# bqcopter.net
KiCad netlist of a schematic drawn in EAGLE
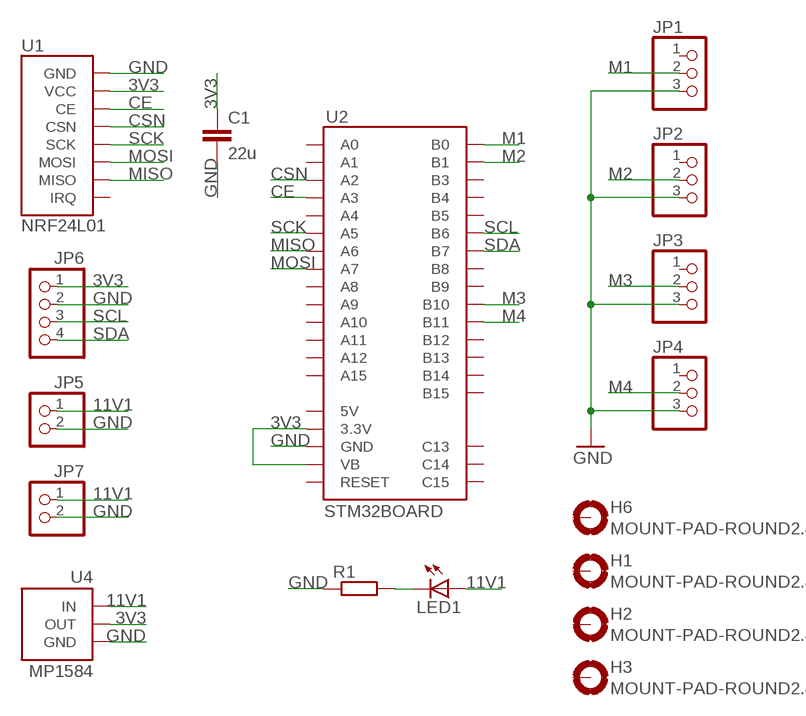
[diagram p0: schematic, sheet 1]

(export (version "E")
  (design (tool "Eeschema 10.0.6"))
  (components
    (comp (ref "C1")
      (value "22u")
      (footprint "eagle-import:C0805")
      (libsource (lib "eagle-import") (part "C-EUC0805"))
    )
    (comp (ref "H1")
      (value "MOUNT-PAD-ROUND2.8")
      (footprint "eagle-import:2,8-PAD")
      (libsource (lib "eagle-import") (part "MOUNT-PAD-ROUND2.8"))
    )
    (comp (ref "H2")
      (value "MOUNT-PAD-ROUND2.8")
      (footprint "eagle-import:2,8-PAD")
      (libsource (lib "eagle-import") (part "MOUNT-PAD-ROUND2.8"))
    )
    (comp (ref "H3")
      (value "MOUNT-PAD-ROUND2.8")
      (footprint "eagle-import:2,8-PAD")
      (libsource (lib "eagle-import") (part "MOUNT-PAD-ROUND2.8"))
    )
    (comp (ref "H6")
      (value "MOUNT-PAD-ROUND2.8")
      (footprint "eagle-import:2,8-PAD")
      (libsource (lib "eagle-import") (part "MOUNT-PAD-ROUND2.8"))
    )
    (comp (ref "JP1")
      (value "PINHD-1X3")
      (footprint "eagle-import:1X03")
      (libsource (lib "eagle-import") (part "PINHD-1X3"))
    )
    (comp (ref "JP2")
      (value "PINHD-1X3")
      (footprint "eagle-import:1X03")
      (libsource (lib "eagle-import") (part "PINHD-1X3"))
    )
    (comp (ref "JP3")
      (value "PINHD-1X3")
      (footprint "eagle-import:1X03")
      (libsource (lib "eagle-import") (part "PINHD-1X3"))
    )
    (comp (ref "JP4")
      (value "PINHD-1X3")
      (footprint "eagle-import:1X03")
      (libsource (lib "eagle-import") (part "PINHD-1X3"))
    )
    (comp (ref "JP5")
      (value "PINHD-1X2")
      (footprint "eagle-import:1X02")
      (libsource (lib "eagle-import") (part "PINHD-1X2"))
    )
    (comp (ref "JP6")
      (value "PINHD-1X4")
      (footprint "eagle-import:1X04")
      (libsource (lib "eagle-import") (part "PINHD-1X4"))
    )
    (comp (ref "JP7")
      (value "PINHD-1X2")
      (footprint "eagle-import:1X02")
      (libsource (lib "eagle-import") (part "PINHD-1X2"))
    )
    (comp (ref "LED1")
      (value "LED3MM")
      (footprint "eagle-import:LED3MM")
      (libsource (lib "eagle-import") (part "LED3MM"))
    )
    (comp (ref "R1")
      (value "R-EU_M0805")
      (footprint "eagle-import:M0805")
      (libsource (lib "eagle-import") (part "R-EU_M0805"))
    )
    (comp (ref "U1")
      (value "NRF24L01")
      (footprint "eagle-import:NRF24L01")
      (libsource (lib "eagle-import") (part "NRF24L01"))
    )
    (comp (ref "U2")
      (value "STM32BOARD")
      (footprint "eagle-import:STM32BOARD")
      (libsource (lib "eagle-import") (part "STM32BOARD"))
    )
    (comp (ref "U4")
      (value "MP1584")
      (footprint "eagle-import:MP1584")
      (libsource (lib "eagle-import") (part "MP1584"))
    )
  )
  (nets
    (net (code "1") (name "/3V3") (class "Default")
      (node (ref "C1") (pin "1") (pinfunction "1_1") (pintype "passive"))
      (node (ref "JP6") (pin "1") (pinfunction "1_1") (pintype "passive"))
      (node (ref "U1") (pin "2") (pinfunction "VCC_2") (pintype "bidirectional"))
      (node (ref "U2") (pin "3.3V_1") (pinfunction "3.3V_3.3V_1") (pintype "bidirectional"))
      (node (ref "U2") (pin "3.3V_2") (pinfunction "3.3V_3.3V_2") (pintype "bidirectional"))
      (node (ref "U2") (pin "VB") (pinfunction "VB_VB") (pintype "bidirectional"))
      (node (ref "U4") (pin "OUT+1") (pinfunction "OUT_OUT+1") (pintype "bidirectional"))
      (node (ref "U4") (pin "OUT+2") (pinfunction "OUT_OUT+2") (pintype "bidirectional"))
    )
    (net (code "2") (name "/11V1") (class "Default")
      (node (ref "JP5") (pin "1") (pinfunction "1_1") (pintype "passive"))
      (node (ref "JP7") (pin "1") (pinfunction "1_1") (pintype "passive"))
      (node (ref "LED1") (pin "A") (pinfunction "A_A") (pintype "passive"))
      (node (ref "U4") (pin "IN+1") (pinfunction "IN_IN+1") (pintype "bidirectional"))
      (node (ref "U4") (pin "IN+2") (pinfunction "IN_IN+2") (pintype "bidirectional"))
    )
    (net (code "3") (name "/CE") (class "Default")
      (node (ref "U1") (pin "3") (pinfunction "CE_3") (pintype "bidirectional"))
      (node (ref "U2") (pin "A3") (pinfunction "A3_A3") (pintype "bidirectional"))
    )
    (net (code "4") (name "/CSN") (class "Default")
      (node (ref "U1") (pin "4") (pinfunction "CSN_4") (pintype "bidirectional"))
      (node (ref "U2") (pin "A2") (pinfunction "A2_A2") (pintype "bidirectional"))
    )
    (net (code "5") (name "/M1") (class "Default")
      (node (ref "JP1") (pin "2") (pinfunction "2_2") (pintype "passive"))
      (node (ref "U2") (pin "B0") (pinfunction "B0_B0") (pintype "bidirectional"))
    )
    (net (code "6") (name "/M2") (class "Default")
      (node (ref "JP2") (pin "2") (pinfunction "2_2") (pintype "passive"))
      (node (ref "U2") (pin "B1") (pinfunction "B1_B1") (pintype "bidirectional"))
    )
    (net (code "7") (name "/M3") (class "Default")
      (node (ref "JP3") (pin "2") (pinfunction "2_2") (pintype "passive"))
      (node (ref "U2") (pin "B10") (pinfunction "B10_B10") (pintype "bidirectional"))
    )
    (net (code "8") (name "/M4") (class "Default")
      (node (ref "JP4") (pin "2") (pinfunction "2_2") (pintype "passive"))
      (node (ref "U2") (pin "B11") (pinfunction "B11_B11") (pintype "bidirectional"))
    )
    (net (code "9") (name "/MISO") (class "Default")
      (node (ref "U1") (pin "7") (pinfunction "MISO_7") (pintype "bidirectional"))
      (node (ref "U2") (pin "A6") (pinfunction "A6_A6") (pintype "bidirectional"))
    )
    (net (code "10") (name "/MOSI") (class "Default")
      (node (ref "U1") (pin "6") (pinfunction "MOSI_6") (pintype "bidirectional"))
      (node (ref "U2") (pin "A7") (pinfunction "A7_A7") (pintype "bidirectional"))
    )
    (net (code "11") (name "/SCK") (class "Default")
      (node (ref "U1") (pin "5") (pinfunction "SCK_5") (pintype "bidirectional"))
      (node (ref "U2") (pin "A5") (pinfunction "A5_A5") (pintype "bidirectional"))
    )
    (net (code "12") (name "/SCL") (class "Default")
      (node (ref "JP6") (pin "3") (pinfunction "3_3") (pintype "passive"))
      (node (ref "U2") (pin "B6") (pinfunction "B6_B6") (pintype "bidirectional"))
    )
    (net (code "13") (name "/SDA") (class "Default")
      (node (ref "JP6") (pin "4") (pinfunction "4_4") (pintype "passive"))
      (node (ref "U2") (pin "B7") (pinfunction "B7_B7") (pintype "bidirectional"))
    )
    (net (code "14") (name "GND") (class "Default")
      (node (ref "C1") (pin "2") (pinfunction "2_2") (pintype "passive"))
      (node (ref "JP1") (pin "3") (pinfunction "3_3") (pintype "passive"))
      (node (ref "JP2") (pin "3") (pinfunction "3_3") (pintype "passive"))
      (node (ref "JP3") (pin "3") (pinfunction "3_3") (pintype "passive"))
      (node (ref "JP4") (pin "3") (pinfunction "3_3") (pintype "passive"))
      (node (ref "JP5") (pin "2") (pinfunction "2_2") (pintype "passive"))
      (node (ref "JP6") (pin "2") (pinfunction "2_2") (pintype "passive"))
      (node (ref "JP7") (pin "2") (pinfunction "2_2") (pintype "passive"))
      (node (ref "R1") (pin "1") (pinfunction "1_1") (pintype "passive"))
      (node (ref "U1") (pin "1") (pinfunction "GND_1") (pintype "bidirectional"))
      (node (ref "U2") (pin "GND_1") (pinfunction "GND_GND_1") (pintype "bidirectional"))
      (node (ref "U2") (pin "GND_2") (pinfunction "GND_GND_2") (pintype "bidirectional"))
      (node (ref "U2") (pin "GND_3") (pinfunction "GND_GND_3") (pintype "bidirectional"))
      (node (ref "U4") (pin "IN-1") (pinfunction "GND_IN-1") (pintype "bidirectional"))
      (node (ref "U4") (pin "IN-2") (pinfunction "GND_IN-2") (pintype "bidirectional"))
      (node (ref "U4") (pin "OUT-1") (pinfunction "GND_OUT-1") (pintype "bidirectional"))
      (node (ref "U4") (pin "OUT-2") (pinfunction "GND_OUT-2") (pintype "bidirectional"))
    )
    (net (code "15") (name "Net-(LED1-C)") (class "Default")
      (node (ref "LED1") (pin "K") (pinfunction "C_K") (pintype "passive"))
      (node (ref "R1") (pin "2") (pinfunction "2_2") (pintype "passive"))
    )
    (net (code "16") (name "unconnected-(H1-MOUNT-PadB2,8)") (class "Default")
      (node (ref "H1") (pin "B2,8") (pinfunction "MOUNT_B2,8") (pintype "passive"))
    )
    (net (code "17") (name "unconnected-(H2-MOUNT-PadB2,8)") (class "Default")
      (node (ref "H2") (pin "B2,8") (pinfunction "MOUNT_B2,8") (pintype "passive"))
    )
    (net (code "18") (name "unconnected-(H3-MOUNT-PadB2,8)") (class "Default")
      (node (ref "H3") (pin "B2,8") (pinfunction "MOUNT_B2,8") (pintype "passive"))
    )
    (net (code "19") (name "unconnected-(H6-MOUNT-PadB2,8)") (class "Default")
      (node (ref "H6") (pin "B2,8") (pinfunction "MOUNT_B2,8") (pintype "passive"))
    )
    (net (code "20") (name "unconnected-(JP1-Pad1)") (class "Default")
      (node (ref "JP1") (pin "1") (pinfunction "1_1") (pintype "passive"))
    )
    (net (code "21") (name "unconnected-(JP2-Pad1)") (class "Default")
      (node (ref "JP2") (pin "1") (pinfunction "1_1") (pintype "passive"))
    )
    (net (code "22") (name "unconnected-(JP3-Pad1)") (class "Default")
      (node (ref "JP3") (pin "1") (pinfunction "1_1") (pintype "passive"))
    )
    (net (code "23") (name "unconnected-(JP4-Pad1)") (class "Default")
      (node (ref "JP4") (pin "1") (pinfunction "1_1") (pintype "passive"))
    )
    (net (code "24") (name "unconnected-(U1-IRQ-Pad8)") (class "Default")
      (node (ref "U1") (pin "8") (pinfunction "IRQ_8") (pintype "bidirectional"))
    )
    (net (code "25") (name "unconnected-(U2-Pad5V)") (class "Default")
      (node (ref "U2") (pin "5V") (pinfunction "5V_5V") (pintype "bidirectional"))
    )
    (net (code "26") (name "unconnected-(U2-PadA0)") (class "Default")
      (node (ref "U2") (pin "A0") (pinfunction "A0_A0") (pintype "bidirectional"))
    )
    (net (code "27") (name "unconnected-(U2-PadA1)") (class "Default")
      (node (ref "U2") (pin "A1") (pinfunction "A1_A1") (pintype "bidirectional"))
    )
    (net (code "28") (name "unconnected-(U2-PadA4)") (class "Default")
      (node (ref "U2") (pin "A4") (pinfunction "A4_A4") (pintype "bidirectional"))
    )
    (net (code "29") (name "unconnected-(U2-PadA8)") (class "Default")
      (node (ref "U2") (pin "A8") (pinfunction "A8_A8") (pintype "bidirectional"))
    )
    (net (code "30") (name "unconnected-(U2-PadA9)") (class "Default")
      (node (ref "U2") (pin "A9") (pinfunction "A9_A9") (pintype "bidirectional"))
    )
    (net (code "31") (name "unconnected-(U2-PadA10)") (class "Default")
      (node (ref "U2") (pin "A10") (pinfunction "A10_A10") (pintype "bidirectional"))
    )
    (net (code "32") (name "unconnected-(U2-PadA11)") (class "Default")
      (node (ref "U2") (pin "A11") (pinfunction "A11_A11") (pintype "bidirectional"))
    )
    (net (code "33") (name "unconnected-(U2-PadA12)") (class "Default")
      (node (ref "U2") (pin "A12") (pinfunction "A12_A12") (pintype "bidirectional"))
    )
    (net (code "34") (name "unconnected-(U2-PadA15)") (class "Default")
      (node (ref "U2") (pin "A15") (pinfunction "A15_A15") (pintype "bidirectional"))
    )
    (net (code "35") (name "unconnected-(U2-PadB3)") (class "Default")
      (node (ref "U2") (pin "B3") (pinfunction "B3_B3") (pintype "bidirectional"))
    )
    (net (code "36") (name "unconnected-(U2-PadB4)") (class "Default")
      (node (ref "U2") (pin "B4") (pinfunction "B4_B4") (pintype "bidirectional"))
    )
    (net (code "37") (name "unconnected-(U2-PadB5)") (class "Default")
      (node (ref "U2") (pin "B5") (pinfunction "B5_B5") (pintype "bidirectional"))
    )
    (net (code "38") (name "unconnected-(U2-PadB8)") (class "Default")
      (node (ref "U2") (pin "B8") (pinfunction "B8_B8") (pintype "bidirectional"))
    )
    (net (code "39") (name "unconnected-(U2-PadB9)") (class "Default")
      (node (ref "U2") (pin "B9") (pinfunction "B9_B9") (pintype "bidirectional"))
    )
    (net (code "40") (name "unconnected-(U2-PadB12)") (class "Default")
      (node (ref "U2") (pin "B12") (pinfunction "B12_B12") (pintype "bidirectional"))
    )
    (net (code "41") (name "unconnected-(U2-PadB13)") (class "Default")
      (node (ref "U2") (pin "B13") (pinfunction "B13_B13") (pintype "bidirectional"))
    )
    (net (code "42") (name "unconnected-(U2-PadB14)") (class "Default")
      (node (ref "U2") (pin "B14") (pinfunction "B14_B14") (pintype "bidirectional"))
    )
    (net (code "43") (name "unconnected-(U2-PadB15)") (class "Default")
      (node (ref "U2") (pin "B15") (pinfunction "B15_B15") (pintype "bidirectional"))
    )
    (net (code "44") (name "unconnected-(U2-PadC13)") (class "Default")
      (node (ref "U2") (pin "C13") (pinfunction "C13_C13") (pintype "bidirectional"))
    )
    (net (code "45") (name "unconnected-(U2-PadC14)") (class "Default")
      (node (ref "U2") (pin "C14") (pinfunction "C14_C14") (pintype "bidirectional"))
    )
    (net (code "46") (name "unconnected-(U2-PadC15)") (class "Default")
      (node (ref "U2") (pin "C15") (pinfunction "C15_C15") (pintype "bidirectional"))
    )
    (net (code "47") (name "unconnected-(U2-PadRESET)") (class "Default")
      (node (ref "U2") (pin "RESET") (pinfunction "RESET_RESET") (pintype "bidirectional"))
    )
  )
)
